# Cashstick.net
KiCad netlist of a schematic drawn in Altium Designer
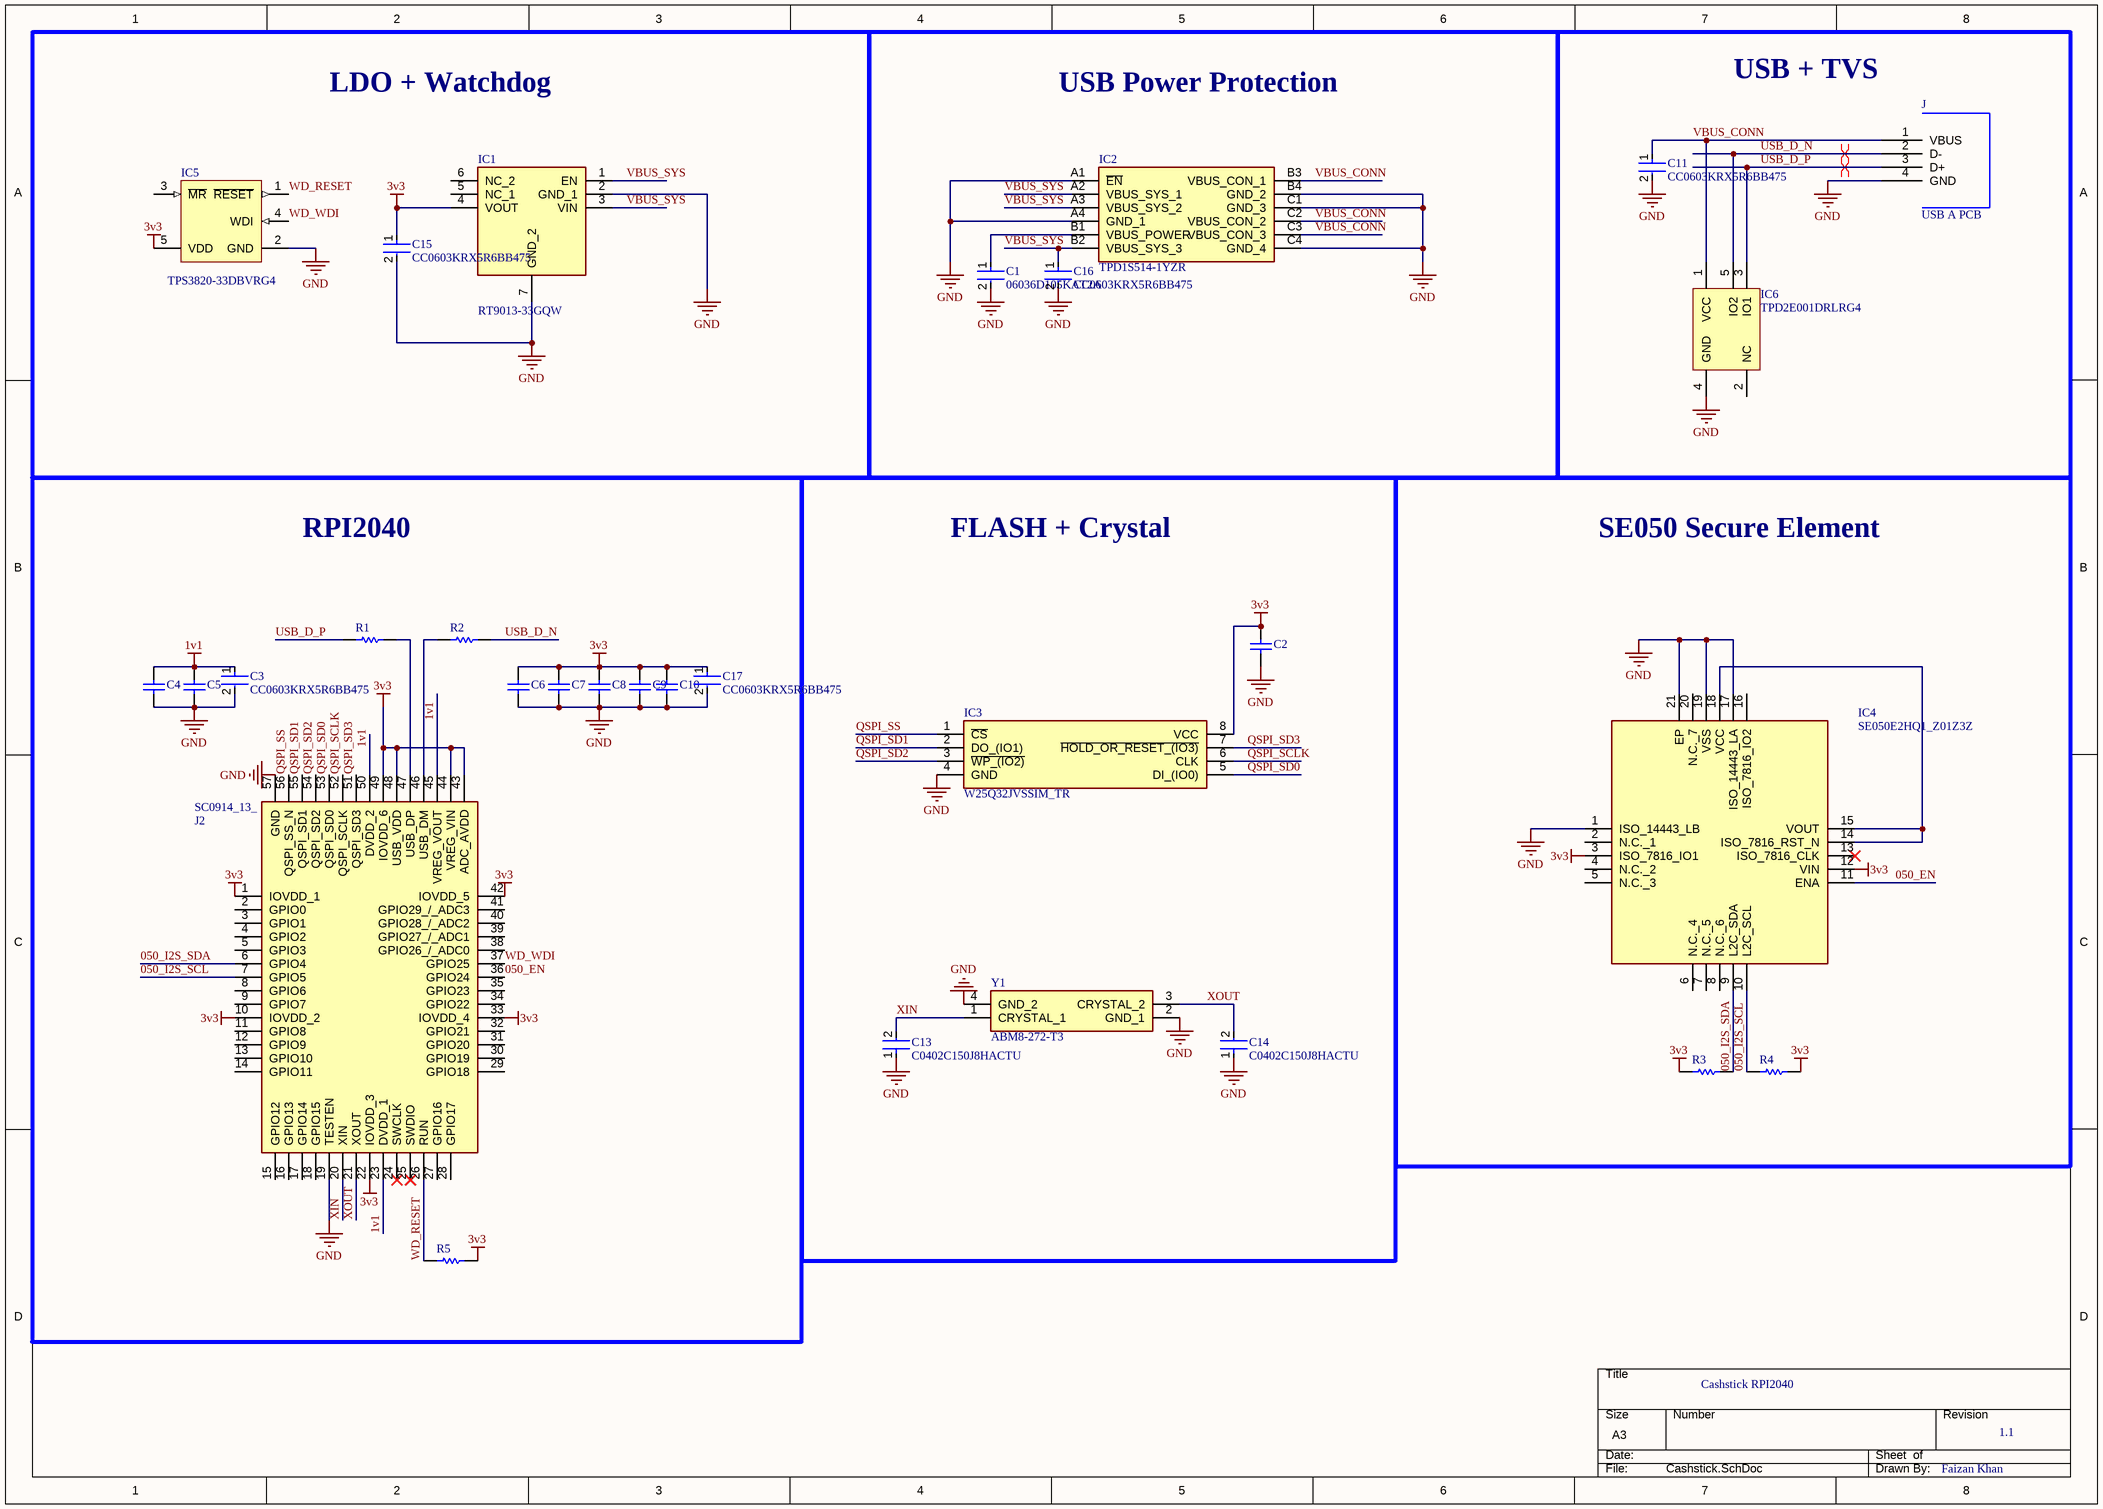
[diagram p0: Cashstick.SchDoc]

(export (version "E")
  (design (tool "Eeschema 10.0.6"))
  (components
    (comp (ref "C1")
      (value "06036D105KAT2A")
      (footprint "FP-0603-L_1_6_0_15-W_0_81-IPC_A")
      (description "General Purpose Ceramic Capacitor, 0603, 1uF, 10%, X5R, 15%, 6.3V")
      (fields (field (name "VOLTAGE") "6.3V") (field (name "TOLERANCE") "10%"))
      (libsource (lib "Altium Content Vault") (part "02cd4be3c70576c341d710602a673aa"))
    )
    (comp (ref "C2")
      (value "0402YC104JAT2A")
      (footprint "CAPC1005X56X25LL10T15")
      (fields (field (name "MANUFACTURER") "AVX Interconnect / Elco"))
      (libsource (lib "Altium Content Vault") (part "CAP"))
    )
    (comp (ref "C3")
      (value "CC0603KRX5R6BB475")
      (footprint "FP-CC0603-DA-MFG")
      (description "CAP CER 4.7UF 10V X5R 0603")
      (fields (field (name "VOLTAGE") "10 V") (field (name "MANUFACTURER") "YAGEO"))
      (libsource (lib "Altium Content Vault") (part "11868f565c42a9108669ba33697ecf6"))
    )
    (comp (ref "C4")
      (value "0402YC104JAT2A")
      (footprint "CAPC1005X56X25LL10T15")
      (fields (field (name "MANUFACTURER") "AVX Interconnect / Elco"))
      (libsource (lib "Altium Content Vault") (part "CAP"))
    )
    (comp (ref "C5")
      (value "0402YC104JAT2A")
      (footprint "CAPC1005X56X25LL10T15")
      (fields (field (name "MANUFACTURER") "AVX Interconnect / Elco"))
      (libsource (lib "Altium Content Vault") (part "CAP"))
    )
    (comp (ref "C6")
      (value "0402YC104JAT2A")
      (footprint "CAPC1005X56X25LL10T15")
      (fields (field (name "MANUFACTURER") "AVX Interconnect / Elco"))
      (libsource (lib "Altium Content Vault") (part "CAP"))
    )
    (comp (ref "C7")
      (value "0402YC104JAT2A")
      (footprint "CAPC1005X56X25LL10T15")
      (fields (field (name "MANUFACTURER") "AVX Interconnect / Elco"))
      (libsource (lib "Altium Content Vault") (part "CAP"))
    )
    (comp (ref "C8")
      (value "0402YC104JAT2A")
      (footprint "CAPC1005X56X25LL10T15")
      (fields (field (name "MANUFACTURER") "AVX Interconnect / Elco"))
      (libsource (lib "Altium Content Vault") (part "CAP"))
    )
    (comp (ref "C9")
      (value "0402YC104JAT2A")
      (footprint "CAPC1005X56X25LL10T15")
      (fields (field (name "MANUFACTURER") "AVX Interconnect / Elco"))
      (libsource (lib "Altium Content Vault") (part "CAP"))
    )
    (comp (ref "C10")
      (value "0402YC104JAT2A")
      (footprint "CAPC1005X56X25LL10T15")
      (fields (field (name "MANUFACTURER") "AVX Interconnect / Elco"))
      (libsource (lib "Altium Content Vault") (part "CAP"))
    )
    (comp (ref "C11")
      (value "CC0603KRX5R6BB475")
      (footprint "FP-CC0603-DA-MFG")
      (description "CAP CER 4.7UF 10V X5R 0603")
      (fields (field (name "VOLTAGE") "10 V") (field (name "MANUFACTURER") "YAGEO"))
      (libsource (lib "Altium Content Vault") (part "11868f565c42a9108669ba33697ecf6"))
    )
    (comp (ref "C13")
      (value "C0402C150J8HACTU")
      (footprint "FP-C0402-BB-MFG")
      (description "C0402 15 pF X8R 5.00% 10 V")
      (fields
        (field (name "OCTOPART") "https://octopart.com/c0402c150j8hactu-kemet-88724175")
        (field (name "TOLERANCE") "0.05")
      )
      (libsource (lib "Altium Content Vault") (part "b4654b650e69147ec39a6b967a45e02"))
    )
    (comp (ref "C14")
      (value "C0402C150J8HACTU")
      (footprint "FP-C0402-BB-MFG")
      (description "C0402 15 pF X8R 5.00% 10 V")
      (fields
        (field (name "OCTOPART") "https://octopart.com/c0402c150j8hactu-kemet-88724175")
        (field (name "TOLERANCE") "0.05")
      )
      (libsource (lib "Altium Content Vault") (part "b4654b650e69147ec39a6b967a45e02"))
    )
    (comp (ref "C15")
      (value "CC0603KRX5R6BB475")
      (footprint "FP-CC0603-DA-MFG")
      (description "CAP CER 4.7UF 10V X5R 0603")
      (fields (field (name "VOLTAGE") "10 V") (field (name "MANUFACTURER") "YAGEO"))
      (libsource (lib "Altium Content Vault") (part "11868f565c42a9108669ba33697ecf6"))
    )
    (comp (ref "C16")
      (value "CC0603KRX5R6BB475")
      (footprint "FP-CC0603-DA-MFG")
      (description "CAP CER 4.7UF 10V X5R 0603")
      (fields (field (name "VOLTAGE") "10 V") (field (name "MANUFACTURER") "YAGEO"))
      (libsource (lib "Altium Content Vault") (part "11868f565c42a9108669ba33697ecf6"))
    )
    (comp (ref "C17")
      (value "CC0603KRX5R6BB475")
      (footprint "FP-CC0603-DA-MFG")
      (description "CAP CER 4.7UF 10V X5R 0603")
      (fields (field (name "VOLTAGE") "10 V") (field (name "MANUFACTURER") "YAGEO"))
      (libsource (lib "Altium Content Vault") (part "11868f565c42a9108669ba33697ecf6"))
    )
    (comp (ref "IC1")
      (value "RT9013-33GQW")
      (footprint "PcbLib1:SON65P200X200X80-7N")
      (description "Integrated Circuit")
      (fields (field (name "MOUSER PART NUMBER") "835-RT9013-33GQW"))
      (libsource (lib "*") (part "RT9013-33GQW"))
    )
    (comp (ref "IC2")
      (value "TPD1S514-1YZR")
      (footprint "PcbLib1:BGA12C40P4X3_199X129X62")
      (description "Integrated Circuit")
      (fields (field (name "MOUSER PART NUMBER") "595-TPD1S514-1YZR"))
      (libsource (lib "*") (part "TPD1S514-1YZR"))
    )
    (comp (ref "IC3")
      (value "W25Q32JVSSIM_TR")
      (footprint "PcbLib1:SOIC127P790X216-8N")
      (description "Integrated Circuit")
      (fields
        (field (name "MANUFACTURER_PART_NUMBER") "W25Q32JVSSIM TR")
        (field (name "MOUSER PART NUMBER") "454-W25Q32JVSSIMTR")
      )
      (libsource (lib "*") (part "W25Q32JVSSIM_TR"))
    )
    (comp (ref "IC4")
      (value "SE050E2HQ1_Z01Z3Z")
      (footprint "PcbLib1:QFN40P300X300X33-21N-D")
      (description "Integrated Circuit")
      (fields
        (field (name "MANUFACTURER_PART_NUMBER") "SE050E2HQ1/Z01Z3Z")
        (field (name "MOUSER PART NUMBER") "771-SE050E2HQ1Z01Z3Z")
      )
      (libsource (lib "*") (part "SE050E2HQ1_Z01Z3Z"))
    )
    (comp (ref "IC5")
      (value "TPS3820-33DBVRG4")
      (footprint "TI-DBV5_V")
      (fields (field (name "MANUFACTURER") "Texas Instruments"))
      (libsource (lib "Altium Content Vault") (part "TI-TPS3820-33DBV5"))
    )
    (comp (ref "IC6")
      (value "TPD2E001DRLRG4")
      (footprint "DRL0005A_L")
      (fields (field (name "MANUFACTURER") "Texas Instruments"))
      (libsource (lib "Altium Content Vault") (part "TI-TPD2E001-SOT_DRL-5"))
    )
    (comp (ref "J")
      (value "USB A PCB")
      (footprint "USB PCB TRACE")
      (libsource (lib "Schlib1") (part "USB A PCB"))
    )
    (comp (ref "J2")
      (value "SC0914_13_")
      (footprint "PcbLib1:SC091413")
      (description "Connector")
      (fields
        (field (name "MANUFACTURER_PART_NUMBER") "SC0914(13)")
        (field (name "MOUSER PART NUMBER") "358-SC091413")
      )
      (libsource (lib "*") (part "SC0914_13_"))
    )
    (comp (ref "R1")
      (value "CR0402-FX-27R4GLF")
      (footprint "RESC1005X40X25ML10T10")
      (fields (field (name "MANUFACTURER") "Bourns"))
      (libsource (lib "Altium Content Vault") (part "RES"))
    )
    (comp (ref "R2")
      (value "CR0402-FX-27R4GLF")
      (footprint "RESC1005X40X25ML10T10")
      (fields (field (name "MANUFACTURER") "Bourns"))
      (libsource (lib "Altium Content Vault") (part "RES"))
    )
    (comp (ref "R3")
      (value "2K2 5% 0402(1005)")
      (footprint "RESC0402(1005)_N")
      (description "2K2 0.063W 5% 0402 (1005 Metric)  SMD")
      (fields (field (name "TOLERANCE") "5 %") (field (name "POWER") "0.063 W"))
      (libsource (lib "Altium Content Vault") (part "RES"))
    )
    (comp (ref "R4")
      (value "2K2 5% 0402(1005)")
      (footprint "RESC0402(1005)_N")
      (description "2K2 0.063W 5% 0402 (1005 Metric)  SMD")
      (fields (field (name "TOLERANCE") "5 %") (field (name "POWER") "0.063 W"))
      (libsource (lib "Altium Content Vault") (part "RES"))
    )
    (comp (ref "R5")
      (value "TNPW040210K0DEED")
      (footprint "RESC1005X40X20NL05T10")
      (fields (field (name "MANUFACTURER") "Vishay BCcomponents"))
      (libsource (lib "Altium Content Vault") (part "RES"))
    )
    (comp (ref "Y1")
      (value "ABM8-272-T3")
      (footprint "PcbLib1:ABM8272T3")
      (description "Crystal or Oscillator")
      (fields (field (name "MOUSER PART NUMBER") "815-ABM8-272-T3"))
      (libsource (lib "*") (part "ABM8-272-T3"))
    )
  )
  (nets
    (net (code "1") (name "/050_EN") (class "Default")
      (node (ref "IC4") (pin "11") (pinfunction "ENA_11") (pintype "passive"))
      (node (ref "J2") (pin "36") (pinfunction "GPIO24_36") (pintype "passive"))
    )
    (net (code "2") (name "/050_I2S_SCL") (class "Default")
      (node (ref "IC4") (pin "10") (pinfunction "L2C_SCL_10") (pintype "passive"))
      (node (ref "J2") (pin "7") (pinfunction "GPIO5_7") (pintype "passive"))
      (node (ref "R4") (pin "1") (pinfunction "1_1") (pintype "passive"))
    )
    (net (code "3") (name "/050_I2S_SDA") (class "Default")
      (node (ref "IC4") (pin "9") (pinfunction "L2C_SDA_9") (pintype "passive"))
      (node (ref "J2") (pin "6") (pinfunction "GPIO4_6") (pintype "passive"))
      (node (ref "R3") (pin "2") (pinfunction "2_2") (pintype "passive"))
    )
    (net (code "4") (name "/QSPI_SCLK") (class "Default")
      (node (ref "IC3") (pin "6") (pinfunction "CLK_6") (pintype "passive"))
      (node (ref "J2") (pin "52") (pinfunction "QSPI_SCLK_52") (pintype "passive"))
    )
    (net (code "5") (name "/QSPI_SD0") (class "Default")
      (node (ref "IC3") (pin "5") (pinfunction "DI_(IO0)_5") (pintype "passive"))
      (node (ref "J2") (pin "53") (pinfunction "QSPI_SD0_53") (pintype "passive"))
    )
    (net (code "6") (name "/QSPI_SD1") (class "Default")
      (node (ref "IC3") (pin "2") (pinfunction "DO_(IO1)_2") (pintype "passive"))
      (node (ref "J2") (pin "55") (pinfunction "QSPI_SD1_55") (pintype "passive"))
    )
    (net (code "7") (name "/QSPI_SD2") (class "Default")
      (node (ref "IC3") (pin "3") (pinfunction "~{WP_(IO2)}_3") (pintype "passive"))
      (node (ref "J2") (pin "54") (pinfunction "QSPI_SD2_54") (pintype "passive"))
    )
    (net (code "8") (name "/QSPI_SD3") (class "Default")
      (node (ref "IC3") (pin "7") (pinfunction "~{HOLD_OR_RESET_(IO3)}_7") (pintype "passive"))
      (node (ref "J2") (pin "51") (pinfunction "QSPI_SD3_51") (pintype "passive"))
    )
    (net (code "9") (name "/QSPI_SS") (class "Default")
      (node (ref "IC3") (pin "1") (pinfunction "~{CS}_1") (pintype "passive"))
      (node (ref "J2") (pin "56") (pinfunction "QSPI_SS_N_56") (pintype "passive"))
    )
    (net (code "10") (name "/USB_D_N") (class "Default")
      (node (ref "IC6") (pin "5") (pinfunction "IO2_5") (pintype "passive"))
      (node (ref "J") (pin "2") (pinfunction "D-_2") (pintype "passive"))
      (node (ref "R2") (pin "2") (pinfunction "2_2") (pintype "passive"))
    )
    (net (code "11") (name "/USB_D_P") (class "Default")
      (node (ref "IC6") (pin "3") (pinfunction "IO1_3") (pintype "passive"))
      (node (ref "J") (pin "3") (pinfunction "D+_3") (pintype "passive"))
      (node (ref "R1") (pin "1") (pinfunction "1_1") (pintype "passive"))
    )
    (net (code "12") (name "/VBUS_CONN") (class "Default")
      (node (ref "C11") (pin "1") (pinfunction "1_1") (pintype "passive"))
      (node (ref "IC2") (pin "B3") (pinfunction "VBUS_CON_1_B3") (pintype "passive"))
      (node (ref "IC2") (pin "C2") (pinfunction "VBUS_CON_2_C2") (pintype "passive"))
      (node (ref "IC2") (pin "C3") (pinfunction "VBUS_CON_3_C3") (pintype "passive"))
      (node (ref "IC6") (pin "1") (pinfunction "VCC_1") (pintype "power_in"))
      (node (ref "J") (pin "1") (pinfunction "VBUS_1") (pintype "passive"))
    )
    (net (code "13") (name "/VBUS_SYS") (class "Default")
      (node (ref "C16") (pin "1") (pinfunction "1_1") (pintype "passive"))
      (node (ref "IC1") (pin "1") (pinfunction "EN_1") (pintype "passive"))
      (node (ref "IC1") (pin "3") (pinfunction "VIN_3") (pintype "passive"))
      (node (ref "IC2") (pin "A2") (pinfunction "VBUS_SYS_1_A2") (pintype "passive"))
      (node (ref "IC2") (pin "A3") (pinfunction "VBUS_SYS_2_A3") (pintype "passive"))
      (node (ref "IC2") (pin "B2") (pinfunction "VBUS_SYS_3_B2") (pintype "passive"))
    )
    (net (code "14") (name "/WD_RESET") (class "Default")
      (node (ref "IC5") (pin "1") (pinfunction "~{RESET}_1") (pintype "output"))
      (node (ref "J2") (pin "26") (pinfunction "RUN_26") (pintype "passive"))
      (node (ref "R5") (pin "1") (pinfunction "1_1") (pintype "passive"))
    )
    (net (code "15") (name "/WD_WDI") (class "Default")
      (node (ref "IC5") (pin "4") (pinfunction "WDI_4") (pintype "input"))
      (node (ref "J2") (pin "37") (pinfunction "GPIO25_37") (pintype "passive"))
    )
    (net (code "16") (name "/XIN") (class "Default")
      (node (ref "C13") (pin "2") (pinfunction "2_2") (pintype "passive"))
      (node (ref "J2") (pin "20") (pinfunction "XIN_20") (pintype "passive"))
      (node (ref "Y1") (pin "1") (pinfunction "CRYSTAL_1_1") (pintype "passive"))
    )
    (net (code "17") (name "/XOUT") (class "Default")
      (node (ref "C14") (pin "2") (pinfunction "2_2") (pintype "passive"))
      (node (ref "J2") (pin "21") (pinfunction "XOUT_21") (pintype "passive"))
      (node (ref "Y1") (pin "3") (pinfunction "CRYSTAL_2_3") (pintype "passive"))
    )
    (net (code "18") (name "1v1") (class "Default")
      (node (ref "C3") (pin "1") (pinfunction "1_1") (pintype "passive"))
      (node (ref "C4") (pin "2") (pinfunction "2_2") (pintype "passive"))
      (node (ref "C5") (pin "2") (pinfunction "2_2") (pintype "passive"))
      (node (ref "J2") (pin "23") (pinfunction "DVDD_1_23") (pintype "passive"))
      (node (ref "J2") (pin "45") (pinfunction "VREG_VOUT_45") (pintype "passive"))
      (node (ref "J2") (pin "50") (pinfunction "DVDD_2_50") (pintype "passive"))
    )
    (net (code "19") (name "3v3") (class "Default")
      (node (ref "C10") (pin "2") (pinfunction "2_2") (pintype "passive"))
      (node (ref "C15") (pin "1") (pinfunction "1_1") (pintype "passive"))
      (node (ref "C17") (pin "1") (pinfunction "1_1") (pintype "passive"))
      (node (ref "C2") (pin "2") (pinfunction "2_2") (pintype "passive"))
      (node (ref "C6") (pin "2") (pinfunction "2_2") (pintype "passive"))
      (node (ref "C7") (pin "2") (pinfunction "2_2") (pintype "passive"))
      (node (ref "C8") (pin "2") (pinfunction "2_2") (pintype "passive"))
      (node (ref "C9") (pin "2") (pinfunction "2_2") (pintype "passive"))
      (node (ref "IC1") (pin "4") (pinfunction "VOUT_4") (pintype "passive"))
      (node (ref "IC3") (pin "8") (pinfunction "VCC_8") (pintype "passive"))
      (node (ref "IC4") (pin "12") (pinfunction "VIN_12") (pintype "passive"))
      (node (ref "IC4") (pin "3") (pinfunction "ISO_7816_IO1_3") (pintype "passive"))
      (node (ref "IC5") (pin "5") (pinfunction "VDD_5") (pintype "power_in"))
      (node (ref "J2") (pin "1") (pinfunction "IOVDD_1_1") (pintype "passive"))
      (node (ref "J2") (pin "10") (pinfunction "IOVDD_2_10") (pintype "passive"))
      (node (ref "J2") (pin "22") (pinfunction "IOVDD_3_22") (pintype "passive"))
      (node (ref "J2") (pin "33") (pinfunction "IOVDD_4_33") (pintype "passive"))
      (node (ref "J2") (pin "42") (pinfunction "IOVDD_5_42") (pintype "passive"))
      (node (ref "J2") (pin "43") (pinfunction "ADC_AVDD_43") (pintype "passive"))
      (node (ref "J2") (pin "44") (pinfunction "VREG_VIN_44") (pintype "passive"))
      (node (ref "J2") (pin "48") (pinfunction "USB_VDD_48") (pintype "passive"))
      (node (ref "J2") (pin "49") (pinfunction "IOVDD_6_49") (pintype "passive"))
      (node (ref "R3") (pin "1") (pinfunction "1_1") (pintype "passive"))
      (node (ref "R4") (pin "2") (pinfunction "2_2") (pintype "passive"))
      (node (ref "R5") (pin "2") (pinfunction "2_2") (pintype "passive"))
    )
    (net (code "20") (name "GND") (class "Default")
      (node (ref "C1") (pin "2") (pinfunction "2_2") (pintype "passive"))
      (node (ref "C10") (pin "1") (pinfunction "1_1") (pintype "passive"))
      (node (ref "C11") (pin "2") (pinfunction "2_2") (pintype "passive"))
      (node (ref "C13") (pin "1") (pinfunction "1_1") (pintype "passive"))
      (node (ref "C14") (pin "1") (pinfunction "1_1") (pintype "passive"))
      (node (ref "C15") (pin "2") (pinfunction "2_2") (pintype "passive"))
      (node (ref "C16") (pin "2") (pinfunction "2_2") (pintype "passive"))
      (node (ref "C17") (pin "2") (pinfunction "2_2") (pintype "passive"))
      (node (ref "C2") (pin "1") (pinfunction "1_1") (pintype "passive"))
      (node (ref "C3") (pin "2") (pinfunction "2_2") (pintype "passive"))
      (node (ref "C4") (pin "1") (pinfunction "1_1") (pintype "passive"))
      (node (ref "C5") (pin "1") (pinfunction "1_1") (pintype "passive"))
      (node (ref "C6") (pin "1") (pinfunction "1_1") (pintype "passive"))
      (node (ref "C7") (pin "1") (pinfunction "1_1") (pintype "passive"))
      (node (ref "C8") (pin "1") (pinfunction "1_1") (pintype "passive"))
      (node (ref "C9") (pin "1") (pinfunction "1_1") (pintype "passive"))
      (node (ref "IC1") (pin "2") (pinfunction "GND_1_2") (pintype "passive"))
      (node (ref "IC1") (pin "7") (pinfunction "GND_2_7") (pintype "passive"))
      (node (ref "IC2") (pin "A1") (pinfunction "~{EN}_A1") (pintype "passive"))
      (node (ref "IC2") (pin "A4") (pinfunction "GND_1_A4") (pintype "passive"))
      (node (ref "IC2") (pin "B4") (pinfunction "GND_2_B4") (pintype "passive"))
      (node (ref "IC2") (pin "C1") (pinfunction "GND_3_C1") (pintype "passive"))
      (node (ref "IC2") (pin "C4") (pinfunction "GND_4_C4") (pintype "passive"))
      (node (ref "IC3") (pin "4") (pinfunction "GND_4") (pintype "passive"))
      (node (ref "IC4") (pin "1") (pinfunction "ISO_14443_LB_1") (pintype "passive"))
      (node (ref "IC4") (pin "17") (pinfunction "ISO_14443_LA_17") (pintype "passive"))
      (node (ref "IC4") (pin "19") (pinfunction "VSS_19") (pintype "passive"))
      (node (ref "IC4") (pin "21") (pinfunction "EP_21") (pintype "passive"))
      (node (ref "IC5") (pin "2") (pinfunction "GND_2") (pintype "power_in"))
      (node (ref "IC6") (pin "4") (pinfunction "GND_4") (pintype "power_in"))
      (node (ref "J") (pin "4") (pinfunction "GND_4") (pintype "passive"))
      (node (ref "J2") (pin "19") (pinfunction "TESTEN_19") (pintype "passive"))
      (node (ref "J2") (pin "57") (pinfunction "GND_57") (pintype "passive"))
      (node (ref "Y1") (pin "2") (pinfunction "GND_1_2") (pintype "passive"))
      (node (ref "Y1") (pin "4") (pinfunction "GND_2_4") (pintype "passive"))
    )
    (net (code "21") (name "Net-(IC2-VBUS_POWER)") (class "Default")
      (node (ref "C1") (pin "1") (pinfunction "1_1") (pintype "passive"))
      (node (ref "IC2") (pin "B1") (pinfunction "VBUS_POWER_B1") (pintype "passive"))
    )
    (net (code "22") (name "Net-(IC4-ISO_7816_RST_N)") (class "Default")
      (node (ref "IC4") (pin "14") (pinfunction "ISO_7816_RST_N_14") (pintype "passive"))
      (node (ref "IC4") (pin "15") (pinfunction "VOUT_15") (pintype "passive"))
      (node (ref "IC4") (pin "18") (pinfunction "VCC_18") (pintype "passive"))
    )
    (net (code "23") (name "Net-(J2-USB_DM)") (class "Default")
      (node (ref "J2") (pin "46") (pinfunction "USB_DM_46") (pintype "passive"))
      (node (ref "R2") (pin "1") (pinfunction "1_1") (pintype "passive"))
    )
    (net (code "24") (name "Net-(J2-USB_DP)") (class "Default")
      (node (ref "J2") (pin "47") (pinfunction "USB_DP_47") (pintype "passive"))
      (node (ref "R1") (pin "2") (pinfunction "2_2") (pintype "passive"))
    )
    (net (code "25") (name "unconnected-(IC1-NC_1-Pad5)") (class "Default")
      (node (ref "IC1") (pin "5") (pinfunction "NC_1_5") (pintype "passive"))
    )
    (net (code "26") (name "unconnected-(IC1-NC_2-Pad6)") (class "Default")
      (node (ref "IC1") (pin "6") (pinfunction "NC_2_6") (pintype "passive"))
    )
    (net (code "27") (name "unconnected-(IC4-ISO_7816_CLK-Pad13)") (class "Default")
      (node (ref "IC4") (pin "13") (pinfunction "ISO_7816_CLK_13") (pintype "passive+no_connect"))
    )
    (net (code "28") (name "unconnected-(IC4-ISO_7816_IO2-Pad16)") (class "Default")
      (node (ref "IC4") (pin "16") (pinfunction "ISO_7816_IO2_16") (pintype "passive"))
    )
    (net (code "29") (name "unconnected-(IC4-N.C._1-Pad2)") (class "Default")
      (node (ref "IC4") (pin "2") (pinfunction "N.C._1_2") (pintype "passive"))
    )
    (net (code "30") (name "unconnected-(IC4-N.C._2-Pad4)") (class "Default")
      (node (ref "IC4") (pin "4") (pinfunction "N.C._2_4") (pintype "passive"))
    )
    (net (code "31") (name "unconnected-(IC4-N.C._3-Pad5)") (class "Default")
      (node (ref "IC4") (pin "5") (pinfunction "N.C._3_5") (pintype "passive"))
    )
    (net (code "32") (name "unconnected-(IC4-N.C._4-Pad6)") (class "Default")
      (node (ref "IC4") (pin "6") (pinfunction "N.C._4_6") (pintype "passive"))
    )
    (net (code "33") (name "unconnected-(IC4-N.C._5-Pad7)") (class "Default")
      (node (ref "IC4") (pin "7") (pinfunction "N.C._5_7") (pintype "passive"))
    )
    (net (code "34") (name "unconnected-(IC4-N.C._6-Pad8)") (class "Default")
      (node (ref "IC4") (pin "8") (pinfunction "N.C._6_8") (pintype "passive"))
    )
    (net (code "35") (name "unconnected-(IC4-N.C._7-Pad20)") (class "Default")
      (node (ref "IC4") (pin "20") (pinfunction "N.C._7_20") (pintype "passive"))
    )
    (net (code "36") (name "unconnected-(IC5-~{MR}-Pad3)") (class "Default")
      (node (ref "IC5") (pin "3") (pinfunction "~{MR}_3") (pintype "input"))
    )
    (net (code "37") (name "unconnected-(IC6-NC-Pad2)") (class "Default")
      (node (ref "IC6") (pin "2") (pinfunction "NC_2") (pintype "passive"))
    )
    (net (code "38") (name "unconnected-(J2-GPIO0-Pad2)") (class "Default")
      (node (ref "J2") (pin "2") (pinfunction "GPIO0_2") (pintype "passive"))
    )
    (net (code "39") (name "unconnected-(J2-GPIO1-Pad3)") (class "Default")
      (node (ref "J2") (pin "3") (pinfunction "GPIO1_3") (pintype "passive"))
    )
    (net (code "40") (name "unconnected-(J2-GPIO2-Pad4)") (class "Default")
      (node (ref "J2") (pin "4") (pinfunction "GPIO2_4") (pintype "passive"))
    )
    (net (code "41") (name "unconnected-(J2-GPIO3-Pad5)") (class "Default")
      (node (ref "J2") (pin "5") (pinfunction "GPIO3_5") (pintype "passive"))
    )
    (net (code "42") (name "unconnected-(J2-GPIO6-Pad8)") (class "Default")
      (node (ref "J2") (pin "8") (pinfunction "GPIO6_8") (pintype "passive"))
    )
    (net (code "43") (name "unconnected-(J2-GPIO7-Pad9)") (class "Default")
      (node (ref "J2") (pin "9") (pinfunction "GPIO7_9") (pintype "passive"))
    )
    (net (code "44") (name "unconnected-(J2-GPIO8-Pad11)") (class "Default")
      (node (ref "J2") (pin "11") (pinfunction "GPIO8_11") (pintype "passive"))
    )
    (net (code "45") (name "unconnected-(J2-GPIO9-Pad12)") (class "Default")
      (node (ref "J2") (pin "12") (pinfunction "GPIO9_12") (pintype "passive"))
    )
    (net (code "46") (name "unconnected-(J2-GPIO10-Pad13)") (class "Default")
      (node (ref "J2") (pin "13") (pinfunction "GPIO10_13") (pintype "passive"))
    )
    (net (code "47") (name "unconnected-(J2-GPIO11-Pad14)") (class "Default")
      (node (ref "J2") (pin "14") (pinfunction "GPIO11_14") (pintype "passive"))
    )
    (net (code "48") (name "unconnected-(J2-GPIO12-Pad15)") (class "Default")
      (node (ref "J2") (pin "15") (pinfunction "GPIO12_15") (pintype "passive"))
    )
    (net (code "49") (name "unconnected-(J2-GPIO13-Pad16)") (class "Default")
      (node (ref "J2") (pin "16") (pinfunction "GPIO13_16") (pintype "passive"))
    )
    (net (code "50") (name "unconnected-(J2-GPIO14-Pad17)") (class "Default")
      (node (ref "J2") (pin "17") (pinfunction "GPIO14_17") (pintype "passive"))
    )
    (net (code "51") (name "unconnected-(J2-GPIO15-Pad18)") (class "Default")
      (node (ref "J2") (pin "18") (pinfunction "GPIO15_18") (pintype "passive"))
    )
    (net (code "52") (name "unconnected-(J2-GPIO16-Pad27)") (class "Default")
      (node (ref "J2") (pin "27") (pinfunction "GPIO16_27") (pintype "passive"))
    )
    (net (code "53") (name "unconnected-(J2-GPIO17-Pad28)") (class "Default")
      (node (ref "J2") (pin "28") (pinfunction "GPIO17_28") (pintype "passive"))
    )
    (net (code "54") (name "unconnected-(J2-GPIO18-Pad29)") (class "Default")
      (node (ref "J2") (pin "29") (pinfunction "GPIO18_29") (pintype "passive"))
    )
    (net (code "55") (name "unconnected-(J2-GPIO19-Pad30)") (class "Default")
      (node (ref "J2") (pin "30") (pinfunction "GPIO19_30") (pintype "passive"))
    )
    (net (code "56") (name "unconnected-(J2-GPIO20-Pad31)") (class "Default")
      (node (ref "J2") (pin "31") (pinfunction "GPIO20_31") (pintype "passive"))
    )
    (net (code "57") (name "unconnected-(J2-GPIO21-Pad32)") (class "Default")
      (node (ref "J2") (pin "32") (pinfunction "GPIO21_32") (pintype "passive"))
    )
    (net (code "58") (name "unconnected-(J2-GPIO22-Pad34)") (class "Default")
      (node (ref "J2") (pin "34") (pinfunction "GPIO22_34") (pintype "passive"))
    )
    (net (code "59") (name "unconnected-(J2-GPIO23-Pad35)") (class "Default")
      (node (ref "J2") (pin "35") (pinfunction "GPIO23_35") (pintype "passive"))
    )
    (net (code "60") (name "unconnected-(J2-GPIO26_{slash}_ADC0-Pad38)") (class "Default")
      (node (ref "J2") (pin "38") (pinfunction "GPIO26_/_ADC0_38") (pintype "passive"))
    )
    (net (code "61") (name "unconnected-(J2-GPIO27_{slash}_ADC1-Pad39)") (class "Default")
      (node (ref "J2") (pin "39") (pinfunction "GPIO27_/_ADC1_39") (pintype "passive"))
    )
    (net (code "62") (name "unconnected-(J2-GPIO28_{slash}_ADC2-Pad40)") (class "Default")
      (node (ref "J2") (pin "40") (pinfunction "GPIO28_/_ADC2_40") (pintype "passive"))
    )
    (net (code "63") (name "unconnected-(J2-GPIO29_{slash}_ADC3-Pad41)") (class "Default")
      (node (ref "J2") (pin "41") (pinfunction "GPIO29_/_ADC3_41") (pintype "passive"))
    )
    (net (code "64") (name "unconnected-(J2-SWCLK-Pad24)") (class "Default")
      (node (ref "J2") (pin "24") (pinfunction "SWCLK_24") (pintype "passive+no_connect"))
    )
    (net (code "65") (name "unconnected-(J2-SWDIO-Pad25)") (class "Default")
      (node (ref "J2") (pin "25") (pinfunction "SWDIO_25") (pintype "passive+no_connect"))
    )
  )
)
